# FMC_SINGLE_LPC_BREAKOUT_REVC.net
KiCad netlist of a schematic drawn in Altium Designer
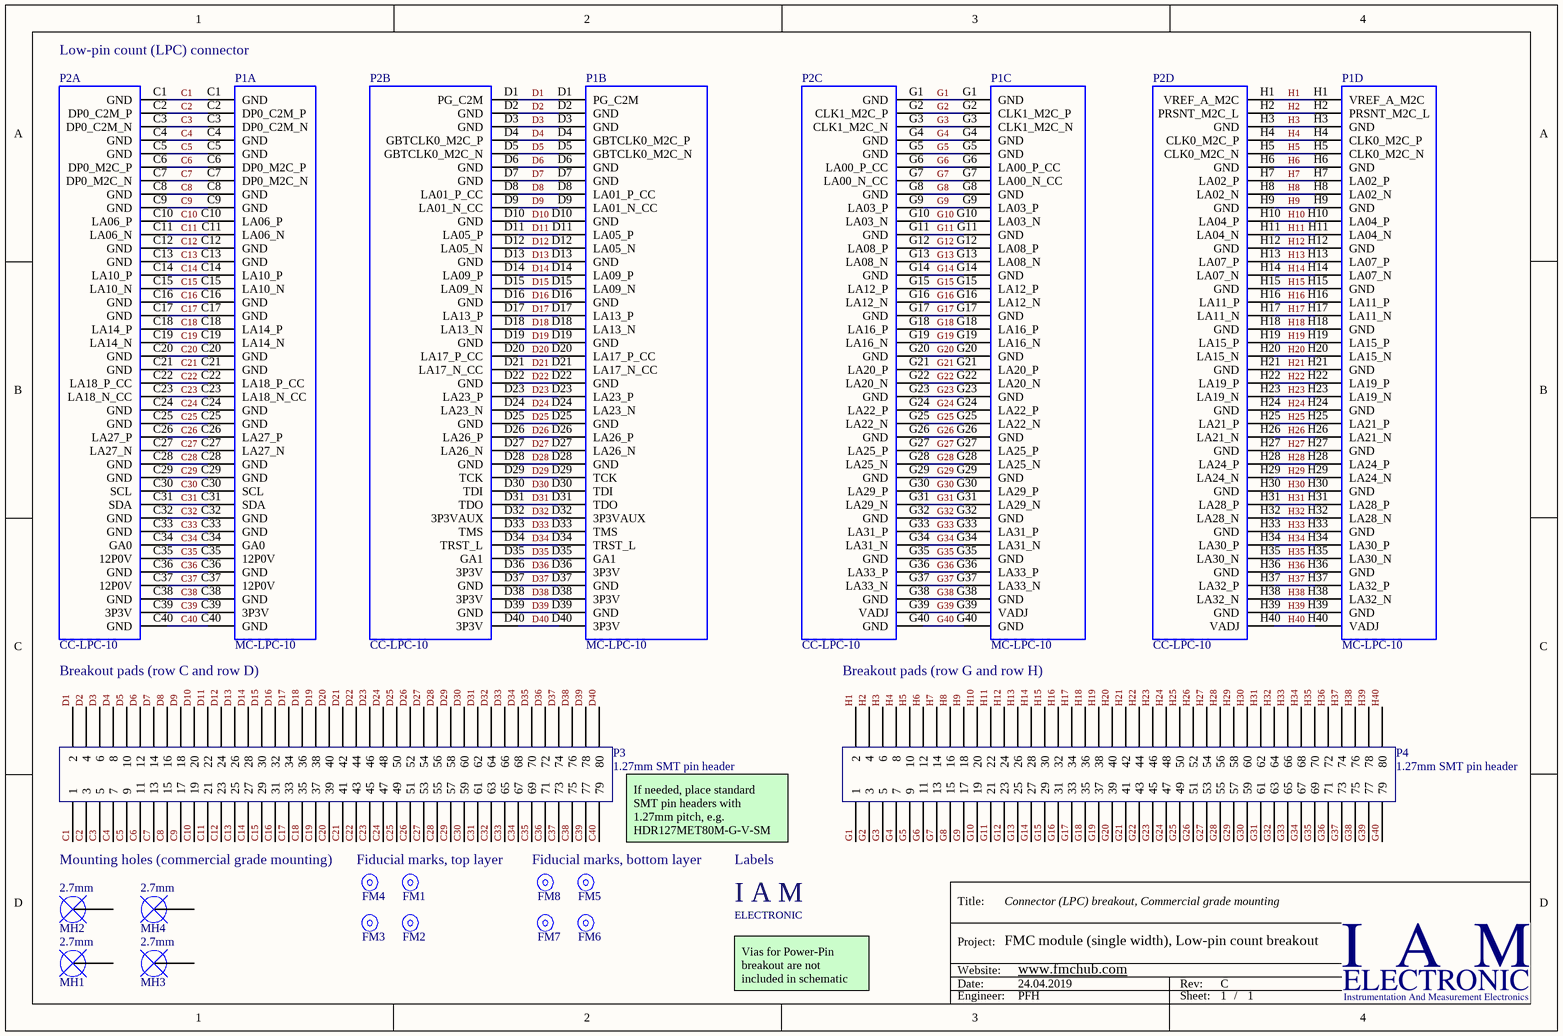
[diagram p0: FMC_SINGLE_LPC_BREAKOUT_REVC.SchDoc]

(export (version "E")
  (design (tool "Eeschema 10.0.6"))
  (components
    (comp (ref "FM1")
      (value "1mm")
      (footprint "FIDUCIAL_MARK_ROUND_RING")
      (description "Fiducial mark, width 1mm, clearance 3mm")
      (libsource (lib "VITA_57_FMC") (part "Fiducial_Mark"))
    )
    (comp (ref "FM2")
      (value "1mm")
      (footprint "FIDUCIAL_MARK_ROUND_RING")
      (description "Fiducial mark, width 1mm, clearance 3mm")
      (libsource (lib "VITA_57_FMC") (part "Fiducial_Mark"))
    )
    (comp (ref "FM3")
      (value "1mm")
      (footprint "FIDUCIAL_MARK_ROUND_RING")
      (description "Fiducial mark, width 1mm, clearance 3mm")
      (libsource (lib "VITA_57_FMC") (part "Fiducial_Mark"))
    )
    (comp (ref "FM4")
      (value "1mm")
      (footprint "FIDUCIAL_MARK_ROUND_RING")
      (description "Fiducial mark, width 1mm, clearance 3mm")
      (libsource (lib "VITA_57_FMC") (part "Fiducial_Mark"))
    )
    (comp (ref "FM5")
      (value "1mm")
      (footprint "FIDUCIAL_MARK_ROUND_RING")
      (description "Fiducial mark, width 1mm, clearance 3mm")
      (libsource (lib "VITA_57_FMC") (part "Fiducial_Mark"))
    )
    (comp (ref "FM6")
      (value "1mm")
      (footprint "FIDUCIAL_MARK_ROUND_RING")
      (description "Fiducial mark, width 1mm, clearance 3mm")
      (libsource (lib "VITA_57_FMC") (part "Fiducial_Mark"))
    )
    (comp (ref "FM7")
      (value "1mm")
      (footprint "FIDUCIAL_MARK_ROUND_RING")
      (description "Fiducial mark, width 1mm, clearance 3mm")
      (libsource (lib "VITA_57_FMC") (part "Fiducial_Mark"))
    )
    (comp (ref "FM8")
      (value "1mm")
      (footprint "FIDUCIAL_MARK_ROUND_RING")
      (description "Fiducial mark, width 1mm, clearance 3mm")
      (libsource (lib "VITA_57_FMC") (part "Fiducial_Mark"))
    )
    (comp (ref "MH1")
      (value "2.7mm")
      (footprint "Mounting_Hole_Plated_2.7mm - d3.1mm")
      (description "Mounting hole, hole size 2.7mm")
      (libsource (lib "VITA_57_FMC") (part "Mounting_Hole_2.7mm"))
    )
    (comp (ref "MH2")
      (value "2.7mm")
      (footprint "Mounting_Hole_Plated_2.7mm - d3.1mm")
      (description "Mounting hole, hole size 2.7mm")
      (libsource (lib "VITA_57_FMC") (part "Mounting_Hole_2.7mm"))
    )
    (comp (ref "MH3")
      (value "2.7mm")
      (footprint "Mounting_Hole_Plated_2.7mm-COVERED")
      (description "Mounting hole, hole size 2.7mm")
      (libsource (lib "VITA_57_FMC") (part "Mounting_Hole_2.7mm"))
    )
    (comp (ref "MH4")
      (value "2.7mm")
      (footprint "Mounting_Hole_Plated_2.7mm-COVERED")
      (description "Mounting hole, hole size 2.7mm")
      (libsource (lib "VITA_57_FMC") (part "Mounting_Hole_2.7mm"))
    )
    (comp (ref "P1")
      (value "MC-LPC-10")
      (footprint "ASP-134604-01")
      (description "MC-LPC-10, FMC Low-pin count connector, lead free, 160 I/Os, male, 10 mm mated stack height")
      (fields (field (name "MANUFACTURER") "Samtec") (field (name "PART") "ASP-134604-01"))
      (libsource (lib "VITA_57_FMC") (part "MC-LPC-10"))
    )
    (comp (ref "P2")
      (value "CC-LPC-10")
      (footprint "ASP-134603-01")
      (description "CC-LPC-10, FMC Low-pin count connector, lead free, 160 I/Os, female, 10 mm mated stack height")
      (fields (field (name "MANUFACTURER") "Samtec") (field (name "PART") "ASP-134603-01"))
      (libsource (lib "VITA_57_FMC") (part "CC-LPC-10"))
    )
    (comp (ref "P3")
      (value "1.27mm SMT pin header")
      (footprint "FTS-140-01-L-DV-A_NO_PASTE")
      (description "1.27 MM 80 PIN VERTICAL MALE HEADER")
      (fields (field (name "PART") "FTS-140-01-L-DV-A") (field (name "MANUFACTURER") "Samtec"))
      (libsource (lib "FTS-140") (part "FTS-140-X-DV"))
    )
    (comp (ref "P4")
      (value "1.27mm SMT pin header")
      (footprint "FTS-140-01-L-DV-A_NO_PASTE")
      (description "1.27 MM 80 PIN VERTICAL MALE HEADER")
      (fields (field (name "PART") "FTS-140-01-L-DV-A") (field (name "MANUFACTURER") "Samtec"))
      (libsource (lib "FTS-140") (part "FTS-140-X-DV"))
    )
    (comp (ref "STR1")
      (value "IAM LOGO")
      (footprint "IAM LOGO - MEDIUM")
      (description "I A M E L E C T R O N I C - Logo")
      (fields (field (name "MANUFACTURER") "IAM ELECTRONIC") (field (name "PART") "Logo"))
      (libsource (lib "IAM_LOGOS") (part "IAM_LOGO"))
    )
  )
  (nets
    (net (code "1") (name "/C1") (class "Default")
      (node (ref "P1") (pin "C1") (pinfunction "GND_C1") (pintype "passive"))
      (node (ref "P2") (pin "C1") (pinfunction "GND_C1") (pintype "passive"))
      (node (ref "P3") (pin "1") (pinfunction "1_1") (pintype "passive"))
    )
    (net (code "2") (name "/C2") (class "Default")
      (node (ref "P1") (pin "C2") (pinfunction "DP0_C2M_P_C2") (pintype "passive"))
      (node (ref "P2") (pin "C2") (pinfunction "DP0_C2M_P_C2") (pintype "passive"))
      (node (ref "P3") (pin "3") (pinfunction "3_3") (pintype "passive"))
    )
    (net (code "3") (name "/C3") (class "Default")
      (node (ref "P1") (pin "C3") (pinfunction "DP0_C2M_N_C3") (pintype "passive"))
      (node (ref "P2") (pin "C3") (pinfunction "DP0_C2M_N_C3") (pintype "passive"))
      (node (ref "P3") (pin "5") (pinfunction "5_5") (pintype "passive"))
    )
    (net (code "4") (name "/C4") (class "Default")
      (node (ref "P1") (pin "C4") (pinfunction "GND_C4") (pintype "passive"))
      (node (ref "P2") (pin "C4") (pinfunction "GND_C4") (pintype "passive"))
      (node (ref "P3") (pin "7") (pinfunction "7_7") (pintype "passive"))
    )
    (net (code "5") (name "/C5") (class "Default")
      (node (ref "P1") (pin "C5") (pinfunction "GND_C5") (pintype "passive"))
      (node (ref "P2") (pin "C5") (pinfunction "GND_C5") (pintype "passive"))
      (node (ref "P3") (pin "9") (pinfunction "9_9") (pintype "passive"))
    )
    (net (code "6") (name "/C6") (class "Default")
      (node (ref "P1") (pin "C6") (pinfunction "DP0_M2C_P_C6") (pintype "passive"))
      (node (ref "P2") (pin "C6") (pinfunction "DP0_M2C_P_C6") (pintype "passive"))
      (node (ref "P3") (pin "11") (pinfunction "11_11") (pintype "passive"))
    )
    (net (code "7") (name "/C7") (class "Default")
      (node (ref "P1") (pin "C7") (pinfunction "DP0_M2C_N_C7") (pintype "passive"))
      (node (ref "P2") (pin "C7") (pinfunction "DP0_M2C_N_C7") (pintype "passive"))
      (node (ref "P3") (pin "13") (pinfunction "13_13") (pintype "passive"))
    )
    (net (code "8") (name "/C8") (class "Default")
      (node (ref "P1") (pin "C8") (pinfunction "GND_C8") (pintype "passive"))
      (node (ref "P2") (pin "C8") (pinfunction "GND_C8") (pintype "passive"))
      (node (ref "P3") (pin "15") (pinfunction "15_15") (pintype "passive"))
    )
    (net (code "9") (name "/C9") (class "Default")
      (node (ref "P1") (pin "C9") (pinfunction "GND_C9") (pintype "passive"))
      (node (ref "P2") (pin "C9") (pinfunction "GND_C9") (pintype "passive"))
      (node (ref "P3") (pin "17") (pinfunction "17_17") (pintype "passive"))
    )
    (net (code "10") (name "/C10") (class "Default")
      (node (ref "P1") (pin "C10") (pinfunction "LA06_P_C10") (pintype "passive"))
      (node (ref "P2") (pin "C10") (pinfunction "LA06_P_C10") (pintype "passive"))
      (node (ref "P3") (pin "19") (pinfunction "19_19") (pintype "passive"))
    )
    (net (code "11") (name "/C11") (class "Default")
      (node (ref "P1") (pin "C11") (pinfunction "LA06_N_C11") (pintype "passive"))
      (node (ref "P2") (pin "C11") (pinfunction "LA06_N_C11") (pintype "passive"))
      (node (ref "P3") (pin "21") (pinfunction "21_21") (pintype "passive"))
    )
    (net (code "12") (name "/C12") (class "Default")
      (node (ref "P1") (pin "C12") (pinfunction "GND_C12") (pintype "passive"))
      (node (ref "P2") (pin "C12") (pinfunction "GND_C12") (pintype "passive"))
      (node (ref "P3") (pin "23") (pinfunction "23_23") (pintype "passive"))
    )
    (net (code "13") (name "/C13") (class "Default")
      (node (ref "P1") (pin "C13") (pinfunction "GND_C13") (pintype "passive"))
      (node (ref "P2") (pin "C13") (pinfunction "GND_C13") (pintype "passive"))
      (node (ref "P3") (pin "25") (pinfunction "25_25") (pintype "passive"))
    )
    (net (code "14") (name "/C14") (class "Default")
      (node (ref "P1") (pin "C14") (pinfunction "LA10_P_C14") (pintype "passive"))
      (node (ref "P2") (pin "C14") (pinfunction "LA10_P_C14") (pintype "passive"))
      (node (ref "P3") (pin "27") (pinfunction "27_27") (pintype "passive"))
    )
    (net (code "15") (name "/C15") (class "Default")
      (node (ref "P1") (pin "C15") (pinfunction "LA10_N_C15") (pintype "passive"))
      (node (ref "P2") (pin "C15") (pinfunction "LA10_N_C15") (pintype "passive"))
      (node (ref "P3") (pin "29") (pinfunction "29_29") (pintype "passive"))
    )
    (net (code "16") (name "/C16") (class "Default")
      (node (ref "P1") (pin "C16") (pinfunction "GND_C16") (pintype "passive"))
      (node (ref "P2") (pin "C16") (pinfunction "GND_C16") (pintype "passive"))
      (node (ref "P3") (pin "31") (pinfunction "31_31") (pintype "passive"))
    )
    (net (code "17") (name "/C17") (class "Default")
      (node (ref "P1") (pin "C17") (pinfunction "GND_C17") (pintype "passive"))
      (node (ref "P2") (pin "C17") (pinfunction "GND_C17") (pintype "passive"))
      (node (ref "P3") (pin "33") (pinfunction "33_33") (pintype "passive"))
    )
    (net (code "18") (name "/C18") (class "Default")
      (node (ref "P1") (pin "C18") (pinfunction "LA14_P_C18") (pintype "passive"))
      (node (ref "P2") (pin "C18") (pinfunction "LA14_P_C18") (pintype "passive"))
      (node (ref "P3") (pin "35") (pinfunction "35_35") (pintype "passive"))
    )
    (net (code "19") (name "/C19") (class "Default")
      (node (ref "P1") (pin "C19") (pinfunction "LA14_N_C19") (pintype "passive"))
      (node (ref "P2") (pin "C19") (pinfunction "LA14_N_C19") (pintype "passive"))
      (node (ref "P3") (pin "37") (pinfunction "37_37") (pintype "passive"))
    )
    (net (code "20") (name "/C20") (class "Default")
      (node (ref "P1") (pin "C20") (pinfunction "GND_C20") (pintype "passive"))
      (node (ref "P2") (pin "C20") (pinfunction "GND_C20") (pintype "passive"))
      (node (ref "P3") (pin "39") (pinfunction "39_39") (pintype "passive"))
    )
    (net (code "21") (name "/C21") (class "Default")
      (node (ref "P1") (pin "C21") (pinfunction "GND_C21") (pintype "passive"))
      (node (ref "P2") (pin "C21") (pinfunction "GND_C21") (pintype "passive"))
      (node (ref "P3") (pin "41") (pinfunction "41_41") (pintype "passive"))
    )
    (net (code "22") (name "/C22") (class "Default")
      (node (ref "P1") (pin "C22") (pinfunction "LA18_P_CC_C22") (pintype "passive"))
      (node (ref "P2") (pin "C22") (pinfunction "LA18_P_CC_C22") (pintype "passive"))
      (node (ref "P3") (pin "43") (pinfunction "43_43") (pintype "passive"))
    )
    (net (code "23") (name "/C23") (class "Default")
      (node (ref "P1") (pin "C23") (pinfunction "LA18_N_CC_C23") (pintype "passive"))
      (node (ref "P2") (pin "C23") (pinfunction "LA18_N_CC_C23") (pintype "passive"))
      (node (ref "P3") (pin "45") (pinfunction "45_45") (pintype "passive"))
    )
    (net (code "24") (name "/C24") (class "Default")
      (node (ref "P1") (pin "C24") (pinfunction "GND_C24") (pintype "passive"))
      (node (ref "P2") (pin "C24") (pinfunction "GND_C24") (pintype "passive"))
      (node (ref "P3") (pin "47") (pinfunction "47_47") (pintype "passive"))
    )
    (net (code "25") (name "/C25") (class "Default")
      (node (ref "P1") (pin "C25") (pinfunction "GND_C25") (pintype "passive"))
      (node (ref "P2") (pin "C25") (pinfunction "GND_C25") (pintype "passive"))
      (node (ref "P3") (pin "49") (pinfunction "49_49") (pintype "passive"))
    )
    (net (code "26") (name "/C26") (class "Default")
      (node (ref "P1") (pin "C26") (pinfunction "LA27_P_C26") (pintype "passive"))
      (node (ref "P2") (pin "C26") (pinfunction "LA27_P_C26") (pintype "passive"))
      (node (ref "P3") (pin "51") (pinfunction "51_51") (pintype "passive"))
    )
    (net (code "27") (name "/C27") (class "Default")
      (node (ref "P1") (pin "C27") (pinfunction "LA27_N_C27") (pintype "passive"))
      (node (ref "P2") (pin "C27") (pinfunction "LA27_N_C27") (pintype "passive"))
      (node (ref "P3") (pin "53") (pinfunction "53_53") (pintype "passive"))
    )
    (net (code "28") (name "/C28") (class "Default")
      (node (ref "P1") (pin "C28") (pinfunction "GND_C28") (pintype "passive"))
      (node (ref "P2") (pin "C28") (pinfunction "GND_C28") (pintype "passive"))
      (node (ref "P3") (pin "55") (pinfunction "55_55") (pintype "passive"))
    )
    (net (code "29") (name "/C29") (class "Default")
      (node (ref "P1") (pin "C29") (pinfunction "GND_C29") (pintype "passive"))
      (node (ref "P2") (pin "C29") (pinfunction "GND_C29") (pintype "passive"))
      (node (ref "P3") (pin "57") (pinfunction "57_57") (pintype "passive"))
    )
    (net (code "30") (name "/C30") (class "Default")
      (node (ref "P1") (pin "C30") (pinfunction "SCL_C30") (pintype "passive"))
      (node (ref "P2") (pin "C30") (pinfunction "SCL_C30") (pintype "passive"))
      (node (ref "P3") (pin "59") (pinfunction "59_59") (pintype "passive"))
    )
    (net (code "31") (name "/C31") (class "Default")
      (node (ref "P1") (pin "C31") (pinfunction "SDA_C31") (pintype "passive"))
      (node (ref "P2") (pin "C31") (pinfunction "SDA_C31") (pintype "passive"))
      (node (ref "P3") (pin "61") (pinfunction "61_61") (pintype "passive"))
    )
    (net (code "32") (name "/C32") (class "Default")
      (node (ref "P1") (pin "C32") (pinfunction "GND_C32") (pintype "passive"))
      (node (ref "P2") (pin "C32") (pinfunction "GND_C32") (pintype "passive"))
      (node (ref "P3") (pin "63") (pinfunction "63_63") (pintype "passive"))
    )
    (net (code "33") (name "/C33") (class "Default")
      (node (ref "P1") (pin "C33") (pinfunction "GND_C33") (pintype "passive"))
      (node (ref "P2") (pin "C33") (pinfunction "GND_C33") (pintype "passive"))
      (node (ref "P3") (pin "65") (pinfunction "65_65") (pintype "passive"))
    )
    (net (code "34") (name "/C34") (class "Default")
      (node (ref "P1") (pin "C34") (pinfunction "GA0_C34") (pintype "passive"))
      (node (ref "P2") (pin "C34") (pinfunction "GA0_C34") (pintype "passive"))
      (node (ref "P3") (pin "67") (pinfunction "67_67") (pintype "passive"))
    )
    (net (code "35") (name "/C35") (class "Default")
      (node (ref "P1") (pin "C35") (pinfunction "12P0V_C35") (pintype "passive"))
      (node (ref "P2") (pin "C35") (pinfunction "12P0V_C35") (pintype "passive"))
      (node (ref "P3") (pin "69") (pinfunction "69_69") (pintype "passive"))
    )
    (net (code "36") (name "/C36") (class "Default")
      (node (ref "P1") (pin "C36") (pinfunction "GND_C36") (pintype "passive"))
      (node (ref "P2") (pin "C36") (pinfunction "GND_C36") (pintype "passive"))
      (node (ref "P3") (pin "71") (pinfunction "71_71") (pintype "passive"))
    )
    (net (code "37") (name "/C37") (class "Default")
      (node (ref "P1") (pin "C37") (pinfunction "12P0V_C37") (pintype "passive"))
      (node (ref "P2") (pin "C37") (pinfunction "12P0V_C37") (pintype "passive"))
      (node (ref "P3") (pin "73") (pinfunction "73_73") (pintype "passive"))
    )
    (net (code "38") (name "/C38") (class "Default")
      (node (ref "P1") (pin "C38") (pinfunction "GND_C38") (pintype "passive"))
      (node (ref "P2") (pin "C38") (pinfunction "GND_C38") (pintype "passive"))
      (node (ref "P3") (pin "75") (pinfunction "75_75") (pintype "passive"))
    )
    (net (code "39") (name "/C39") (class "Default")
      (node (ref "P1") (pin "C39") (pinfunction "3P3V_C39") (pintype "passive"))
      (node (ref "P2") (pin "C39") (pinfunction "3P3V_C39") (pintype "passive"))
      (node (ref "P3") (pin "77") (pinfunction "77_77") (pintype "passive"))
    )
    (net (code "40") (name "/C40") (class "Default")
      (node (ref "P1") (pin "C40") (pinfunction "GND_C40") (pintype "passive"))
      (node (ref "P2") (pin "C40") (pinfunction "GND_C40") (pintype "passive"))
      (node (ref "P3") (pin "79") (pinfunction "79_79") (pintype "passive"))
    )
    (net (code "41") (name "/D1") (class "Default")
      (node (ref "P1") (pin "D1") (pinfunction "PG_C2M_D1") (pintype "passive"))
      (node (ref "P2") (pin "D1") (pinfunction "PG_C2M_D1") (pintype "passive"))
      (node (ref "P3") (pin "2") (pinfunction "2_2") (pintype "passive"))
    )
    (net (code "42") (name "/D2") (class "Default")
      (node (ref "P1") (pin "D2") (pinfunction "GND_D2") (pintype "passive"))
      (node (ref "P2") (pin "D2") (pinfunction "GND_D2") (pintype "passive"))
      (node (ref "P3") (pin "4") (pinfunction "4_4") (pintype "passive"))
    )
    (net (code "43") (name "/D3") (class "Default")
      (node (ref "P1") (pin "D3") (pinfunction "GND_D3") (pintype "passive"))
      (node (ref "P2") (pin "D3") (pinfunction "GND_D3") (pintype "passive"))
      (node (ref "P3") (pin "6") (pinfunction "6_6") (pintype "passive"))
    )
    (net (code "44") (name "/D4") (class "Default")
      (node (ref "P1") (pin "D4") (pinfunction "GBTCLK0_M2C_P_D4") (pintype "passive"))
      (node (ref "P2") (pin "D4") (pinfunction "GBTCLK0_M2C_P_D4") (pintype "passive"))
      (node (ref "P3") (pin "8") (pinfunction "8_8") (pintype "passive"))
    )
    (net (code "45") (name "/D5") (class "Default")
      (node (ref "P1") (pin "D5") (pinfunction "GBTCLK0_M2C_N_D5") (pintype "passive"))
      (node (ref "P2") (pin "D5") (pinfunction "GBTCLK0_M2C_N_D5") (pintype "passive"))
      (node (ref "P3") (pin "10") (pinfunction "10_10") (pintype "passive"))
    )
    (net (code "46") (name "/D6") (class "Default")
      (node (ref "P1") (pin "D6") (pinfunction "GND_D6") (pintype "passive"))
      (node (ref "P2") (pin "D6") (pinfunction "GND_D6") (pintype "passive"))
      (node (ref "P3") (pin "12") (pinfunction "12_12") (pintype "passive"))
    )
    (net (code "47") (name "/D7") (class "Default")
      (node (ref "P1") (pin "D7") (pinfunction "GND_D7") (pintype "passive"))
      (node (ref "P2") (pin "D7") (pinfunction "GND_D7") (pintype "passive"))
      (node (ref "P3") (pin "14") (pinfunction "14_14") (pintype "passive"))
    )
    (net (code "48") (name "/D8") (class "Default")
      (node (ref "P1") (pin "D8") (pinfunction "LA01_P_CC_D8") (pintype "passive"))
      (node (ref "P2") (pin "D8") (pinfunction "LA01_P_CC_D8") (pintype "passive"))
      (node (ref "P3") (pin "16") (pinfunction "16_16") (pintype "passive"))
    )
    (net (code "49") (name "/D9") (class "Default")
      (node (ref "P1") (pin "D9") (pinfunction "LA01_N_CC_D9") (pintype "passive"))
      (node (ref "P2") (pin "D9") (pinfunction "LA01_N_CC_D9") (pintype "passive"))
      (node (ref "P3") (pin "18") (pinfunction "18_18") (pintype "passive"))
    )
    (net (code "50") (name "/D10") (class "Default")
      (node (ref "P1") (pin "D10") (pinfunction "GND_D10") (pintype "passive"))
      (node (ref "P2") (pin "D10") (pinfunction "GND_D10") (pintype "passive"))
      (node (ref "P3") (pin "20") (pinfunction "20_20") (pintype "passive"))
    )
    (net (code "51") (name "/D11") (class "Default")
      (node (ref "P1") (pin "D11") (pinfunction "LA05_P_D11") (pintype "passive"))
      (node (ref "P2") (pin "D11") (pinfunction "LA05_P_D11") (pintype "passive"))
      (node (ref "P3") (pin "22") (pinfunction "22_22") (pintype "passive"))
    )
    (net (code "52") (name "/D12") (class "Default")
      (node (ref "P1") (pin "D12") (pinfunction "LA05_N_D12") (pintype "passive"))
      (node (ref "P2") (pin "D12") (pinfunction "LA05_N_D12") (pintype "passive"))
      (node (ref "P3") (pin "24") (pinfunction "24_24") (pintype "passive"))
    )
    (net (code "53") (name "/D13") (class "Default")
      (node (ref "P1") (pin "D13") (pinfunction "GND_D13") (pintype "passive"))
      (node (ref "P2") (pin "D13") (pinfunction "GND_D13") (pintype "passive"))
      (node (ref "P3") (pin "26") (pinfunction "26_26") (pintype "passive"))
    )
    (net (code "54") (name "/D14") (class "Default")
      (node (ref "P1") (pin "D14") (pinfunction "LA09_P_D14") (pintype "passive"))
      (node (ref "P2") (pin "D14") (pinfunction "LA09_P_D14") (pintype "passive"))
      (node (ref "P3") (pin "28") (pinfunction "28_28") (pintype "passive"))
    )
    (net (code "55") (name "/D15") (class "Default")
      (node (ref "P1") (pin "D15") (pinfunction "LA09_N_D15") (pintype "passive"))
      (node (ref "P2") (pin "D15") (pinfunction "LA09_N_D15") (pintype "passive"))
      (node (ref "P3") (pin "30") (pinfunction "30_30") (pintype "passive"))
    )
    (net (code "56") (name "/D16") (class "Default")
      (node (ref "P1") (pin "D16") (pinfunction "GND_D16") (pintype "passive"))
      (node (ref "P2") (pin "D16") (pinfunction "GND_D16") (pintype "passive"))
      (node (ref "P3") (pin "32") (pinfunction "32_32") (pintype "passive"))
    )
    (net (code "57") (name "/D17") (class "Default")
      (node (ref "P1") (pin "D17") (pinfunction "LA13_P_D17") (pintype "passive"))
      (node (ref "P2") (pin "D17") (pinfunction "LA13_P_D17") (pintype "passive"))
      (node (ref "P3") (pin "34") (pinfunction "34_34") (pintype "passive"))
    )
    (net (code "58") (name "/D18") (class "Default")
      (node (ref "P1") (pin "D18") (pinfunction "LA13_N_D18") (pintype "passive"))
      (node (ref "P2") (pin "D18") (pinfunction "LA13_N_D18") (pintype "passive"))
      (node (ref "P3") (pin "36") (pinfunction "36_36") (pintype "passive"))
    )
    (net (code "59") (name "/D19") (class "Default")
      (node (ref "P1") (pin "D19") (pinfunction "GND_D19") (pintype "passive"))
      (node (ref "P2") (pin "D19") (pinfunction "GND_D19") (pintype "passive"))
      (node (ref "P3") (pin "38") (pinfunction "38_38") (pintype "passive"))
    )
    (net (code "60") (name "/D20") (class "Default")
      (node (ref "P1") (pin "D20") (pinfunction "LA17_P_CC_D20") (pintype "passive"))
      (node (ref "P2") (pin "D20") (pinfunction "LA17_P_CC_D20") (pintype "passive"))
      (node (ref "P3") (pin "40") (pinfunction "40_40") (pintype "passive"))
    )
    (net (code "61") (name "/D21") (class "Default")
      (node (ref "P1") (pin "D21") (pinfunction "LA17_N_CC_D21") (pintype "passive"))
      (node (ref "P2") (pin "D21") (pinfunction "LA17_N_CC_D21") (pintype "passive"))
      (node (ref "P3") (pin "42") (pinfunction "42_42") (pintype "passive"))
    )
    (net (code "62") (name "/D22") (class "Default")
      (node (ref "P1") (pin "D22") (pinfunction "GND_D22") (pintype "passive"))
      (node (ref "P2") (pin "D22") (pinfunction "GND_D22") (pintype "passive"))
      (node (ref "P3") (pin "44") (pinfunction "44_44") (pintype "passive"))
    )
    (net (code "63") (name "/D23") (class "Default")
      (node (ref "P1") (pin "D23") (pinfunction "LA23_P_D23") (pintype "passive"))
      (node (ref "P2") (pin "D23") (pinfunction "LA23_P_D23") (pintype "passive"))
      (node (ref "P3") (pin "46") (pinfunction "46_46") (pintype "passive"))
    )
    (net (code "64") (name "/D24") (class "Default")
      (node (ref "P1") (pin "D24") (pinfunction "LA23_N_D24") (pintype "passive"))
      (node (ref "P2") (pin "D24") (pinfunction "LA23_N_D24") (pintype "passive"))
      (node (ref "P3") (pin "48") (pinfunction "48_48") (pintype "passive"))
    )
    (net (code "65") (name "/D25") (class "Default")
      (node (ref "P1") (pin "D25") (pinfunction "GND_D25") (pintype "passive"))
      (node (ref "P2") (pin "D25") (pinfunction "GND_D25") (pintype "passive"))
      (node (ref "P3") (pin "50") (pinfunction "50_50") (pintype "passive"))
    )
    (net (code "66") (name "/D26") (class "Default")
      (node (ref "P1") (pin "D26") (pinfunction "LA26_P_D26") (pintype "passive"))
      (node (ref "P2") (pin "D26") (pinfunction "LA26_P_D26") (pintype "passive"))
      (node (ref "P3") (pin "52") (pinfunction "52_52") (pintype "passive"))
    )
    (net (code "67") (name "/D27") (class "Default")
      (node (ref "P1") (pin "D27") (pinfunction "LA26_N_D27") (pintype "passive"))
      (node (ref "P2") (pin "D27") (pinfunction "LA26_N_D27") (pintype "passive"))
      (node (ref "P3") (pin "54") (pinfunction "54_54") (pintype "passive"))
    )
    (net (code "68") (name "/D28") (class "Default")
      (node (ref "P1") (pin "D28") (pinfunction "GND_D28") (pintype "passive"))
      (node (ref "P2") (pin "D28") (pinfunction "GND_D28") (pintype "passive"))
      (node (ref "P3") (pin "56") (pinfunction "56_56") (pintype "passive"))
    )
    (net (code "69") (name "/D29") (class "Default")
      (node (ref "P1") (pin "D29") (pinfunction "TCK_D29") (pintype "passive"))
      (node (ref "P2") (pin "D29") (pinfunction "TCK_D29") (pintype "passive"))
      (node (ref "P3") (pin "58") (pinfunction "58_58") (pintype "passive"))
    )
    (net (code "70") (name "/D30") (class "Default")
      (node (ref "P1") (pin "D30") (pinfunction "TDI_D30") (pintype "passive"))
      (node (ref "P2") (pin "D30") (pinfunction "TDI_D30") (pintype "passive"))
      (node (ref "P3") (pin "60") (pinfunction "60_60") (pintype "passive"))
    )
    (net (code "71") (name "/D31") (class "Default")
      (node (ref "P1") (pin "D31") (pinfunction "TDO_D31") (pintype "passive"))
      (node (ref "P2") (pin "D31") (pinfunction "TDO_D31") (pintype "passive"))
      (node (ref "P3") (pin "62") (pinfunction "62_62") (pintype "passive"))
    )
    (net (code "72") (name "/D32") (class "Default")
      (node (ref "P1") (pin "D32") (pinfunction "3P3VAUX_D32") (pintype "passive"))
      (node (ref "P2") (pin "D32") (pinfunction "3P3VAUX_D32") (pintype "passive"))
      (node (ref "P3") (pin "64") (pinfunction "64_64") (pintype "passive"))
    )
    (net (code "73") (name "/D33") (class "Default")
      (node (ref "P1") (pin "D33") (pinfunction "TMS_D33") (pintype "passive"))
      (node (ref "P2") (pin "D33") (pinfunction "TMS_D33") (pintype "passive"))
      (node (ref "P3") (pin "66") (pinfunction "66_66") (pintype "passive"))
    )
    (net (code "74") (name "/D34") (class "Default")
      (node (ref "P1") (pin "D34") (pinfunction "TRST_L_D34") (pintype "passive"))
      (node (ref "P2") (pin "D34") (pinfunction "TRST_L_D34") (pintype "passive"))
      (node (ref "P3") (pin "68") (pinfunction "68_68") (pintype "passive"))
    )
    (net (code "75") (name "/D35") (class "Default")
      (node (ref "P1") (pin "D35") (pinfunction "GA1_D35") (pintype "passive"))
      (node (ref "P2") (pin "D35") (pinfunction "GA1_D35") (pintype "passive"))
      (node (ref "P3") (pin "70") (pinfunction "70_70") (pintype "passive"))
    )
    (net (code "76") (name "/D36") (class "Default")
      (node (ref "P1") (pin "D36") (pinfunction "3P3V_D36") (pintype "passive"))
      (node (ref "P2") (pin "D36") (pinfunction "3P3V_D36") (pintype "passive"))
      (node (ref "P3") (pin "72") (pinfunction "72_72") (pintype "passive"))
    )
    (net (code "77") (name "/D37") (class "Default")
      (node (ref "P1") (pin "D37") (pinfunction "GND_D37") (pintype "passive"))
      (node (ref "P2") (pin "D37") (pinfunction "GND_D37") (pintype "passive"))
      (node (ref "P3") (pin "74") (pinfunction "74_74") (pintype "passive"))
    )
    (net (code "78") (name "/D38") (class "Default")
      (node (ref "P1") (pin "D38") (pinfunction "3P3V_D38") (pintype "passive"))
      (node (ref "P2") (pin "D38") (pinfunction "3P3V_D38") (pintype "passive"))
      (node (ref "P3") (pin "76") (pinfunction "76_76") (pintype "passive"))
    )
    (net (code "79") (name "/D39") (class "Default")
      (node (ref "P1") (pin "D39") (pinfunction "GND_D39") (pintype "passive"))
      (node (ref "P2") (pin "D39") (pinfunction "GND_D39") (pintype "passive"))
      (node (ref "P3") (pin "78") (pinfunction "78_78") (pintype "passive"))
    )
    (net (code "80") (name "/D40") (class "Default")
      (node (ref "P1") (pin "D40") (pinfunction "3P3V_D40") (pintype "passive"))
      (node (ref "P2") (pin "D40") (pinfunction "3P3V_D40") (pintype "passive"))
      (node (ref "P3") (pin "80") (pinfunction "80_80") (pintype "passive"))
    )
    (net (code "81") (name "/G1") (class "Default")
      (node (ref "P1") (pin "G1") (pinfunction "GND_G1") (pintype "passive"))
      (node (ref "P2") (pin "G1") (pinfunction "GND_G1") (pintype "passive"))
      (node (ref "P4") (pin "1") (pinfunction "1_1") (pintype "passive"))
    )
    (net (code "82") (name "/G2") (class "Default")
      (node (ref "P1") (pin "G2") (pinfunction "CLK1_M2C_P_G2") (pintype "passive"))
      (node (ref "P2") (pin "G2") (pinfunction "CLK1_M2C_P_G2") (pintype "passive"))
      (node (ref "P4") (pin "3") (pinfunction "3_3") (pintype "passive"))
    )
    (net (code "83") (name "/G3") (class "Default")
      (node (ref "P1") (pin "G3") (pinfunction "CLK1_M2C_N_G3") (pintype "passive"))
      (node (ref "P2") (pin "G3") (pinfunction "CLK1_M2C_N_G3") (pintype "passive"))
      (node (ref "P4") (pin "5") (pinfunction "5_5") (pintype "passive"))
    )
    (net (code "84") (name "/G4") (class "Default")
      (node (ref "P1") (pin "G4") (pinfunction "GND_G4") (pintype "passive"))
      (node (ref "P2") (pin "G4") (pinfunction "GND_G4") (pintype "passive"))
      (node (ref "P4") (pin "7") (pinfunction "7_7") (pintype "passive"))
    )
    (net (code "85") (name "/G5") (class "Default")
      (node (ref "P1") (pin "G5") (pinfunction "GND_G5") (pintype "passive"))
      (node (ref "P2") (pin "G5") (pinfunction "GND_G5") (pintype "passive"))
      (node (ref "P4") (pin "9") (pinfunction "9_9") (pintype "passive"))
    )
    (net (code "86") (name "/G6") (class "Default")
      (node (ref "P1") (pin "G6") (pinfunction "LA00_P_CC_G6") (pintype "passive"))
      (node (ref "P2") (pin "G6") (pinfunction "LA00_P_CC_G6") (pintype "passive"))
      (node (ref "P4") (pin "11") (pinfunction "11_11") (pintype "passive"))
    )
    (net (code "87") (name "/G7") (class "Default")
      (node (ref "P1") (pin "G7") (pinfunction "LA00_N_CC_G7") (pintype "passive"))
      (node (ref "P2") (pin "G7") (pinfunction "LA00_N_CC_G7") (pintype "passive"))
      (node (ref "P4") (pin "13") (pinfunction "13_13") (pintype "passive"))
    )
    (net (code "88") (name "/G8") (class "Default")
      (node (ref "P1") (pin "G8") (pinfunction "GND_G8") (pintype "passive"))
      (node (ref "P2") (pin "G8") (pinfunction "GND_G8") (pintype "passive"))
      (node (ref "P4") (pin "15") (pinfunction "15_15") (pintype "passive"))
    )
    (net (code "89") (name "/G9") (class "Default")
      (node (ref "P1") (pin "G9") (pinfunction "LA03_P_G9") (pintype "passive"))
      (node (ref "P2") (pin "G9") (pinfunction "LA03_P_G9") (pintype "passive"))
      (node (ref "P4") (pin "17") (pinfunction "17_17") (pintype "passive"))
    )
    (net (code "90") (name "/G10") (class "Default")
      (node (ref "P1") (pin "G10") (pinfunction "LA03_N_G10") (pintype "passive"))
      (node (ref "P2") (pin "G10") (pinfunction "LA03_N_G10") (pintype "passive"))
      (node (ref "P4") (pin "19") (pinfunction "19_19") (pintype "passive"))
    )
    (net (code "91") (name "/G11") (class "Default")
      (node (ref "P1") (pin "G11") (pinfunction "GND_G11") (pintype "passive"))
      (node (ref "P2") (pin "G11") (pinfunction "GND_G11") (pintype "passive"))
      (node (ref "P4") (pin "21") (pinfunction "21_21") (pintype "passive"))
    )
    (net (code "92") (name "/G12") (class "Default")
      (node (ref "P1") (pin "G12") (pinfunction "LA08_P_G12") (pintype "passive"))
      (node (ref "P2") (pin "G12") (pinfunction "LA08_P_G12") (pintype "passive"))
      (node (ref "P4") (pin "23") (pinfunction "23_23") (pintype "passive"))
    )
    (net (code "93") (name "/G13") (class "Default")
      (node (ref "P1") (pin "G13") (pinfunction "LA08_N_G13") (pintype "passive"))
      (node (ref "P2") (pin "G13") (pinfunction "LA08_N_G13") (pintype "passive"))
      (node (ref "P4") (pin "25") (pinfunction "25_25") (pintype "passive"))
    )
    (net (code "94") (name "/G14") (class "Default")
      (node (ref "P1") (pin "G14") (pinfunction "GND_G14") (pintype "passive"))
      (node (ref "P2") (pin "G14") (pinfunction "GND_G14") (pintype "passive"))
      (node (ref "P4") (pin "27") (pinfunction "27_27") (pintype "passive"))
    )
    (net (code "95") (name "/G15") (class "Default")
      (node (ref "P1") (pin "G15") (pinfunction "LA12_P_G15") (pintype "passive"))
      (node (ref "P2") (pin "G15") (pinfunction "LA12_P_G15") (pintype "passive"))
      (node (ref "P4") (pin "29") (pinfunction "29_29") (pintype "passive"))
    )
    (net (code "96") (name "/G16") (class "Default")
      (node (ref "P1") (pin "G16") (pinfunction "LA12_N_G16") (pintype "passive"))
      (node (ref "P2") (pin "G16") (pinfunction "LA12_N_G16") (pintype "passive"))
      (node (ref "P4") (pin "31") (pinfunction "31_31") (pintype "passive"))
    )
    (net (code "97") (name "/G17") (class "Default")
      (node (ref "P1") (pin "G17") (pinfunction "GND_G17") (pintype "passive"))
      (node (ref "P2") (pin "G17") (pinfunction "GND_G17") (pintype "passive"))
      (node (ref "P4") (pin "33") (pinfunction "33_33") (pintype "passive"))
    )
    (net (code "98") (name "/G18") (class "Default")
      (node (ref "P1") (pin "G18") (pinfunction "LA16_P_G18") (pintype "passive"))
      (node (ref "P2") (pin "G18") (pinfunction "LA16_P_G18") (pintype "passive"))
      (node (ref "P4") (pin "35") (pinfunction "35_35") (pintype "passive"))
    )
    (net (code "99") (name "/G19") (class "Default")
      (node (ref "P1") (pin "G19") (pinfunction "LA16_N_G19") (pintype "passive"))
      (node (ref "P2") (pin "G19") (pinfunction "LA16_N_G19") (pintype "passive"))
      (node (ref "P4") (pin "37") (pinfunction "37_37") (pintype "passive"))
    )
    (net (code "100") (name "/G20") (class "Default")
      (node (ref "P1") (pin "G20") (pinfunction "GND_G20") (pintype "passive"))
      (node (ref "P2") (pin "G20") (pinfunction "GND_G20") (pintype "passive"))
      (node (ref "P4") (pin "39") (pinfunction "39_39") (pintype "passive"))
    )
    (net (code "101") (name "/G21") (class "Default")
      (node (ref "P1") (pin "G21") (pinfunction "LA20_P_G21") (pintype "passive"))
      (node (ref "P2") (pin "G21") (pinfunction "LA20_P_G21") (pintype "passive"))
      (node (ref "P4") (pin "41") (pinfunction "41_41") (pintype "passive"))
    )
    (net (code "102") (name "/G22") (class "Default")
      (node (ref "P1") (pin "G22") (pinfunction "LA20_N_G22") (pintype "passive"))
      (node (ref "P2") (pin "G22") (pinfunction "LA20_N_G22") (pintype "passive"))
      (node (ref "P4") (pin "43") (pinfunction "43_43") (pintype "passive"))
    )
    (net (code "103") (name "/G23") (class "Default")
      (node (ref "P1") (pin "G23") (pinfunction "GND_G23") (pintype "passive"))
      (node (ref "P2") (pin "G23") (pinfunction "GND_G23") (pintype "passive"))
      (node (ref "P4") (pin "45") (pinfunction "45_45") (pintype "passive"))
    )
    (net (code "104") (name "/G24") (class "Default")
      (node (ref "P1") (pin "G24") (pinfunction "LA22_P_G24") (pintype "passive"))
      (node (ref "P2") (pin "G24") (pinfunction "LA22_P_G24") (pintype "passive"))
      (node (ref "P4") (pin "47") (pinfunction "47_47") (pintype "passive"))
    )
    (net (code "105") (name "/G25") (class "Default")
      (node (ref "P1") (pin "G25") (pinfunction "LA22_N_G25") (pintype "passive"))
      (node (ref "P2") (pin "G25") (pinfunction "LA22_N_G25") (pintype "passive"))
      (node (ref "P4") (pin "49") (pinfunction "49_49") (pintype "passive"))
    )
    (net (code "106") (name "/G26") (class "Default")
      (node (ref "P1") (pin "G26") (pinfunction "GND_G26") (pintype "passive"))
      (node (ref "P2") (pin "G26") (pinfunction "GND_G26") (pintype "passive"))
      (node (ref "P4") (pin "51") (pinfunction "51_51") (pintype "passive"))
    )
    (net (code "107") (name "/G27") (class "Default")
      (node (ref "P1") (pin "G27") (pinfunction "LA25_P_G27") (pintype "passive"))
      (node (ref "P2") (pin "G27") (pinfunction "LA25_P_G27") (pintype "passive"))
      (node (ref "P4") (pin "53") (pinfunction "53_53") (pintype "passive"))
    )
    (net (code "108") (name "/G28") (class "Default")
      (node (ref "P1") (pin "G28") (pinfunction "LA25_N_G28") (pintype "passive"))
      (node (ref "P2") (pin "G28") (pinfunction "LA25_N_G28") (pintype "passive"))
      (node (ref "P4") (pin "55") (pinfunction "55_55") (pintype "passive"))
    )
    (net (code "109") (name "/G29") (class "Default")
      (node (ref "P1") (pin "G29") (pinfunction "GND_G29") (pintype "passive"))
      (node (ref "P2") (pin "G29") (pinfunction "GND_G29") (pintype "passive"))
      (node (ref "P4") (pin "57") (pinfunction "57_57") (pintype "passive"))
    )
    (net (code "110") (name "/G30") (class "Default")
      (node (ref "P1") (pin "G30") (pinfunction "LA29_P_G30") (pintype "passive"))
      (node (ref "P2") (pin "G30") (pinfunction "LA29_P_G30") (pintype "passive"))
      (node (ref "P4") (pin "59") (pinfunction "59_59") (pintype "passive"))
    )
    (net (code "111") (name "/G31") (class "Default")
      (node (ref "P1") (pin "G31") (pinfunction "LA29_N_G31") (pintype "passive"))
      (node (ref "P2") (pin "G31") (pinfunction "LA29_N_G31") (pintype "passive"))
      (node (ref "P4") (pin "61") (pinfunction "61_61") (pintype "passive"))
    )
    (net (code "112") (name "/G32") (class "Default")
      (node (ref "P1") (pin "G32") (pinfunction "GND_G32") (pintype "passive"))
      (node (ref "P2") (pin "G32") (pinfunction "GND_G32") (pintype "passive"))
      (node (ref "P4") (pin "63") (pinfunction "63_63") (pintype "passive"))
    )
    (net (code "113") (name "/G33") (class "Default")
      (node (ref "P1") (pin "G33") (pinfunction "LA31_P_G33") (pintype "passive"))
      (node (ref "P2") (pin "G33") (pinfunction "LA31_P_G33") (pintype "passive"))
      (node (ref "P4") (pin "65") (pinfunction "65_65") (pintype "passive"))
    )
    (net (code "114") (name "/G34") (class "Default")
      (node (ref "P1") (pin "G34") (pinfunction "LA31_N_G34") (pintype "passive"))
      (node (ref "P2") (pin "G34") (pinfunction "LA31_N_G34") (pintype "passive"))
      (node (ref "P4") (pin "67") (pinfunction "67_67") (pintype "passive"))
    )
    (net (code "115") (name "/G35") (class "Default")
      (node (ref "P1") (pin "G35") (pinfunction "GND_G35") (pintype "passive"))
      (node (ref "P2") (pin "G35") (pinfunction "GND_G35") (pintype "passive"))
      (node (ref "P4") (pin "69") (pinfunction "69_69") (pintype "passive"))
    )
    (net (code "116") (name "/G36") (class "Default")
      (node (ref "P1") (pin "G36") (pinfunction "LA33_P_G36") (pintype "passive"))
      (node (ref "P2") (pin "G36") (pinfunction "LA33_P_G36") (pintype "passive"))
      (node (ref "P4") (pin "71") (pinfunction "71_71") (pintype "passive"))
    )
    (net (code "117") (name "/G37") (class "Default")
      (node (ref "P1") (pin "G37") (pinfunction "LA33_N_G37") (pintype "passive"))
      (node (ref "P2") (pin "G37") (pinfunction "LA33_N_G37") (pintype "passive"))
      (node (ref "P4") (pin "73") (pinfunction "73_73") (pintype "passive"))
    )
    (net (code "118") (name "/G38") (class "Default")
      (node (ref "P1") (pin "G38") (pinfunction "GND_G38") (pintype "passive"))
      (node (ref "P2") (pin "G38") (pinfunction "GND_G38") (pintype "passive"))
      (node (ref "P4") (pin "75") (pinfunction "75_75") (pintype "passive"))
    )
    (net (code "119") (name "/G39") (class "Default")
      (node (ref "P1") (pin "G39") (pinfunction "VADJ_G39") (pintype "passive"))
      (node (ref "P2") (pin "G39") (pinfunction "VADJ_G39") (pintype "passive"))
      (node (ref "P4") (pin "77") (pinfunction "77_77") (pintype "passive"))
    )
    (net (code "120") (name "/G40") (class "Default")
      (node (ref "P1") (pin "G40") (pinfunction "GND_G40") (pintype "passive"))
      (node (ref "P2") (pin "G40") (pinfunction "GND_G40") (pintype "passive"))
      (node (ref "P4") (pin "79") (pinfunction "79_79") (pintype "passive"))
    )
    (net (code "121") (name "/H1") (class "Default")
      (node (ref "P1") (pin "H1") (pinfunction "VREF_A_M2C_H1") (pintype "passive"))
      (node (ref "P2") (pin "H1") (pinfunction "VREF_A_M2C_H1") (pintype "passive"))
      (node (ref "P4") (pin "2") (pinfunction "2_2") (pintype "passive"))
    )
    (net (code "122") (name "/H2") (class "Default")
      (node (ref "P1") (pin "H2") (pinfunction "PRSNT_M2C_L_H2") (pintype "passive"))
      (node (ref "P2") (pin "H2") (pinfunction "PRSNT_M2C_L_H2") (pintype "passive"))
      (node (ref "P4") (pin "4") (pinfunction "4_4") (pintype "passive"))
    )
    (net (code "123") (name "/H3") (class "Default")
      (node (ref "P1") (pin "H3") (pinfunction "GND_H3") (pintype "passive"))
      (node (ref "P2") (pin "H3") (pinfunction "GND_H3") (pintype "passive"))
      (node (ref "P4") (pin "6") (pinfunction "6_6") (pintype "passive"))
    )
    (net (code "124") (name "/H4") (class "Default")
      (node (ref "P1") (pin "H4") (pinfunction "CLK0_M2C_P_H4") (pintype "passive"))
      (node (ref "P2") (pin "H4") (pinfunction "CLK0_M2C_P_H4") (pintype "passive"))
      (node (ref "P4") (pin "8") (pinfunction "8_8") (pintype "passive"))
    )
    (net (code "125") (name "/H5") (class "Default")
      (node (ref "P1") (pin "H5") (pinfunction "CLK0_M2C_N_H5") (pintype "passive"))
      (node (ref "P2") (pin "H5") (pinfunction "CLK0_M2C_N_H5") (pintype "passive"))
      (node (ref "P4") (pin "10") (pinfunction "10_10") (pintype "passive"))
    )
    (net (code "126") (name "/H6") (class "Default")
      (node (ref "P1") (pin "H6") (pinfunction "GND_H6") (pintype "passive"))
      (node (ref "P2") (pin "H6") (pinfunction "GND_H6") (pintype "passive"))
      (node (ref "P4") (pin "12") (pinfunction "12_12") (pintype "passive"))
    )
    (net (code "127") (name "/H7") (class "Default")
      (node (ref "P1") (pin "H7") (pinfunction "LA02_P_H7") (pintype "passive"))
      (node (ref "P2") (pin "H7") (pinfunction "LA02_P_H7") (pintype "passive"))
      (node (ref "P4") (pin "14") (pinfunction "14_14") (pintype "passive"))
    )
    (net (code "128") (name "/H8") (class "Default")
      (node (ref "P1") (pin "H8") (pinfunction "LA02_N_H8") (pintype "passive"))
      (node (ref "P2") (pin "H8") (pinfunction "LA02_N_H8") (pintype "passive"))
      (node (ref "P4") (pin "16") (pinfunction "16_16") (pintype "passive"))
    )
    (net (code "129") (name "/H9") (class "Default")
      (node (ref "P1") (pin "H9") (pinfunction "GND_H9") (pintype "passive"))
      (node (ref "P2") (pin "H9") (pinfunction "GND_H9") (pintype "passive"))
      (node (ref "P4") (pin "18") (pinfunction "18_18") (pintype "passive"))
    )
    (net (code "130") (name "/H10") (class "Default")
      (node (ref "P1") (pin "H10") (pinfunction "LA04_P_H10") (pintype "passive"))
      (node (ref "P2") (pin "H10") (pinfunction "LA04_P_H10") (pintype "passive"))
      (node (ref "P4") (pin "20") (pinfunction "20_20") (pintype "passive"))
    )
    (net (code "131") (name "/H11") (class "Default")
      (node (ref "P1") (pin "H11") (pinfunction "LA04_N_H11") (pintype "passive"))
      (node (ref "P2") (pin "H11") (pinfunction "LA04_N_H11") (pintype "passive"))
      (node (ref "P4") (pin "22") (pinfunction "22_22") (pintype "passive"))
    )
    (net (code "132") (name "/H12") (class "Default")
      (node (ref "P1") (pin "H12") (pinfunction "GND_H12") (pintype "passive"))
      (node (ref "P2") (pin "H12") (pinfunction "GND_H12") (pintype "passive"))
      (node (ref "P4") (pin "24") (pinfunction "24_24") (pintype "passive"))
    )
    (net (code "133") (name "/H13") (class "Default")
      (node (ref "P1") (pin "H13") (pinfunction "LA07_P_H13") (pintype "passive"))
      (node (ref "P2") (pin "H13") (pinfunction "LA07_P_H13") (pintype "passive"))
      (node (ref "P4") (pin "26") (pinfunction "26_26") (pintype "passive"))
    )
    (net (code "134") (name "/H14") (class "Default")
      (node (ref "P1") (pin "H14") (pinfunction "LA07_N_H14") (pintype "passive"))
      (node (ref "P2") (pin "H14") (pinfunction "LA07_N_H14") (pintype "passive"))
      (node (ref "P4") (pin "28") (pinfunction "28_28") (pintype "passive"))
    )
    (net (code "135") (name "/H15") (class "Default")
      (node (ref "P1") (pin "H15") (pinfunction "GND_H15") (pintype "passive"))
      (node (ref "P2") (pin "H15") (pinfunction "GND_H15") (pintype "passive"))
      (node (ref "P4") (pin "30") (pinfunction "30_30") (pintype "passive"))
    )
    (net (code "136") (name "/H16") (class "Default")
      (node (ref "P1") (pin "H16") (pinfunction "LA11_P_H16") (pintype "passive"))
      (node (ref "P2") (pin "H16") (pinfunction "LA11_P_H16") (pintype "passive"))
      (node (ref "P4") (pin "32") (pinfunction "32_32") (pintype "passive"))
    )
    (net (code "137") (name "/H17") (class "Default")
      (node (ref "P1") (pin "H17") (pinfunction "LA11_N_H17") (pintype "passive"))
      (node (ref "P2") (pin "H17") (pinfunction "LA11_N_H17") (pintype "passive"))
      (node (ref "P4") (pin "34") (pinfunction "34_34") (pintype "passive"))
    )
    (net (code "138") (name "/H18") (class "Default")
      (node (ref "P1") (pin "H18") (pinfunction "GND_H18") (pintype "passive"))
      (node (ref "P2") (pin "H18") (pinfunction "GND_H18") (pintype "passive"))
      (node (ref "P4") (pin "36") (pinfunction "36_36") (pintype "passive"))
    )
    (net (code "139") (name "/H19") (class "Default")
      (node (ref "P1") (pin "H19") (pinfunction "LA15_P_H19") (pintype "passive"))
      (node (ref "P2") (pin "H19") (pinfunction "LA15_P_H19") (pintype "passive"))
      (node (ref "P4") (pin "38") (pinfunction "38_38") (pintype "passive"))
    )
    (net (code "140") (name "/H20") (class "Default")
      (node (ref "P1") (pin "H20") (pinfunction "LA15_N_H20") (pintype "passive"))
      (node (ref "P2") (pin "H20") (pinfunction "LA15_N_H20") (pintype "passive"))
      (node (ref "P4") (pin "40") (pinfunction "40_40") (pintype "passive"))
    )
    (net (code "141") (name "/H21") (class "Default")
      (node (ref "P1") (pin "H21") (pinfunction "GND_H21") (pintype "passive"))
      (node (ref "P2") (pin "H21") (pinfunction "GND_H21") (pintype "passive"))
      (node (ref "P4") (pin "42") (pinfunction "42_42") (pintype "passive"))
    )
    (net (code "142") (name "/H22") (class "Default")
      (node (ref "P1") (pin "H22") (pinfunction "LA19_P_H22") (pintype "passive"))
      (node (ref "P2") (pin "H22") (pinfunction "LA19_P_H22") (pintype "passive"))
      (node (ref "P4") (pin "44") (pinfunction "44_44") (pintype "passive"))
    )
    (net (code "143") (name "/H23") (class "Default")
      (node (ref "P1") (pin "H23") (pinfunction "LA19_N_H23") (pintype "passive"))
      (node (ref "P2") (pin "H23") (pinfunction "LA19_N_H23") (pintype "passive"))
      (node (ref "P4") (pin "46") (pinfunction "46_46") (pintype "passive"))
    )
    (net (code "144") (name "/H24") (class "Default")
      (node (ref "P1") (pin "H24") (pinfunction "GND_H24") (pintype "passive"))
      (node (ref "P2") (pin "H24") (pinfunction "GND_H24") (pintype "passive"))
      (node (ref "P4") (pin "48") (pinfunction "48_48") (pintype "passive"))
    )
    (net (code "145") (name "/H25") (class "Default")
      (node (ref "P1") (pin "H25") (pinfunction "LA21_P_H25") (pintype "passive"))
      (node (ref "P2") (pin "H25") (pinfunction "LA21_P_H25") (pintype "passive"))
      (node (ref "P4") (pin "50") (pinfunction "50_50") (pintype "passive"))
    )
    (net (code "146") (name "/H26") (class "Default")
      (node (ref "P1") (pin "H26") (pinfunction "LA21_N_H26") (pintype "passive"))
      (node (ref "P2") (pin "H26") (pinfunction "LA21_N_H26") (pintype "passive"))
      (node (ref "P4") (pin "52") (pinfunction "52_52") (pintype "passive"))
    )
    (net (code "147") (name "/H27") (class "Default")
      (node (ref "P1") (pin "H27") (pinfunction "GND_H27") (pintype "passive"))
      (node (ref "P2") (pin "H27") (pinfunction "GND_H27") (pintype "passive"))
      (node (ref "P4") (pin "54") (pinfunction "54_54") (pintype "passive"))
    )
    (net (code "148") (name "/H28") (class "Default")
      (node (ref "P1") (pin "H28") (pinfunction "LA24_P_H28") (pintype "passive"))
      (node (ref "P2") (pin "H28") (pinfunction "LA24_P_H28") (pintype "passive"))
      (node (ref "P4") (pin "56") (pinfunction "56_56") (pintype "passive"))
    )
    (net (code "149") (name "/H29") (class "Default")
      (node (ref "P1") (pin "H29") (pinfunction "LA24_N_H29") (pintype "passive"))
      (node (ref "P2") (pin "H29") (pinfunction "LA24_N_H29") (pintype "passive"))
      (node (ref "P4") (pin "58") (pinfunction "58_58") (pintype "passive"))
    )
    (net (code "150") (name "/H30") (class "Default")
      (node (ref "P1") (pin "H30") (pinfunction "GND_H30") (pintype "passive"))
      (node (ref "P2") (pin "H30") (pinfunction "GND_H30") (pintype "passive"))
      (node (ref "P4") (pin "60") (pinfunction "60_60") (pintype "passive"))
    )
    (net (code "151") (name "/H31") (class "Default")
      (node (ref "P1") (pin "H31") (pinfunction "LA28_P_H31") (pintype "passive"))
      (node (ref "P2") (pin "H31") (pinfunction "LA28_P_H31") (pintype "passive"))
      (node (ref "P4") (pin "62") (pinfunction "62_62") (pintype "passive"))
    )
    (net (code "152") (name "/H32") (class "Default")
      (node (ref "P1") (pin "H32") (pinfunction "LA28_N_H32") (pintype "passive"))
      (node (ref "P2") (pin "H32") (pinfunction "LA28_N_H32") (pintype "passive"))
      (node (ref "P4") (pin "64") (pinfunction "64_64") (pintype "passive"))
    )
    (net (code "153") (name "/H33") (class "Default")
      (node (ref "P1") (pin "H33") (pinfunction "GND_H33") (pintype "passive"))
      (node (ref "P2") (pin "H33") (pinfunction "GND_H33") (pintype "passive"))
      (node (ref "P4") (pin "66") (pinfunction "66_66") (pintype "passive"))
    )
    (net (code "154") (name "/H34") (class "Default")
      (node (ref "P1") (pin "H34") (pinfunction "LA30_P_H34") (pintype "passive"))
      (node (ref "P2") (pin "H34") (pinfunction "LA30_P_H34") (pintype "passive"))
      (node (ref "P4") (pin "68") (pinfunction "68_68") (pintype "passive"))
    )
    (net (code "155") (name "/H35") (class "Default")
      (node (ref "P1") (pin "H35") (pinfunction "LA30_N_H35") (pintype "passive"))
      (node (ref "P2") (pin "H35") (pinfunction "LA30_N_H35") (pintype "passive"))
      (node (ref "P4") (pin "70") (pinfunction "70_70") (pintype "passive"))
    )
    (net (code "156") (name "/H36") (class "Default")
      (node (ref "P1") (pin "H36") (pinfunction "GND_H36") (pintype "passive"))
      (node (ref "P2") (pin "H36") (pinfunction "GND_H36") (pintype "passive"))
      (node (ref "P4") (pin "72") (pinfunction "72_72") (pintype "passive"))
    )
    (net (code "157") (name "/H37") (class "Default")
      (node (ref "P1") (pin "H37") (pinfunction "LA32_P_H37") (pintype "passive"))
      (node (ref "P2") (pin "H37") (pinfunction "LA32_P_H37") (pintype "passive"))
      (node (ref "P4") (pin "74") (pinfunction "74_74") (pintype "passive"))
    )
    (net (code "158") (name "/H38") (class "Default")
      (node (ref "P1") (pin "H38") (pinfunction "LA32_N_H38") (pintype "passive"))
      (node (ref "P2") (pin "H38") (pinfunction "LA32_N_H38") (pintype "passive"))
      (node (ref "P4") (pin "76") (pinfunction "76_76") (pintype "passive"))
    )
    (net (code "159") (name "/H39") (class "Default")
      (node (ref "P1") (pin "H39") (pinfunction "GND_H39") (pintype "passive"))
      (node (ref "P2") (pin "H39") (pinfunction "GND_H39") (pintype "passive"))
      (node (ref "P4") (pin "78") (pinfunction "78_78") (pintype "passive"))
    )
    (net (code "160") (name "/H40") (class "Default")
      (node (ref "P1") (pin "H40") (pinfunction "VADJ_H40") (pintype "passive"))
      (node (ref "P2") (pin "H40") (pinfunction "VADJ_H40") (pintype "passive"))
      (node (ref "P4") (pin "80") (pinfunction "80_80") (pintype "passive"))
    )
    (net (code "161") (name "unconnected-(FM1-PadFD0)") (class "Default")
      (node (ref "FM1") (pin "FD0") (pinfunction "FD0_FD0") (pintype "passive"))
    )
    (net (code "162") (name "unconnected-(FM2-PadFD0)") (class "Default")
      (node (ref "FM2") (pin "FD0") (pinfunction "FD0_FD0") (pintype "passive"))
    )
    (net (code "163") (name "unconnected-(FM3-PadFD0)") (class "Default")
      (node (ref "FM3") (pin "FD0") (pinfunction "FD0_FD0") (pintype "passive"))
    )
    (net (code "164") (name "unconnected-(FM4-PadFD0)") (class "Default")
      (node (ref "FM4") (pin "FD0") (pinfunction "FD0_FD0") (pintype "passive"))
    )
    (net (code "165") (name "unconnected-(FM5-PadFD0)") (class "Default")
      (node (ref "FM5") (pin "FD0") (pinfunction "FD0_FD0") (pintype "passive"))
    )
    (net (code "166") (name "unconnected-(FM6-PadFD0)") (class "Default")
      (node (ref "FM6") (pin "FD0") (pinfunction "FD0_FD0") (pintype "passive"))
    )
    (net (code "167") (name "unconnected-(FM7-PadFD0)") (class "Default")
      (node (ref "FM7") (pin "FD0") (pinfunction "FD0_FD0") (pintype "passive"))
    )
    (net (code "168") (name "unconnected-(FM8-PadFD0)") (class "Default")
      (node (ref "FM8") (pin "FD0") (pinfunction "FD0_FD0") (pintype "passive"))
    )
    (net (code "169") (name "unconnected-(MH1-Pad0)") (class "Default")
      (node (ref "MH1") (pin "0") (pinfunction "0_0") (pintype "passive"))
    )
    (net (code "170") (name "unconnected-(MH2-Pad0)") (class "Default")
      (node (ref "MH2") (pin "0") (pinfunction "0_0") (pintype "passive"))
    )
    (net (code "171") (name "unconnected-(MH3-Pad0)") (class "Default")
      (node (ref "MH3") (pin "0") (pinfunction "0_0") (pintype "passive"))
    )
    (net (code "172") (name "unconnected-(MH4-Pad0)") (class "Default")
      (node (ref "MH4") (pin "0") (pinfunction "0_0") (pintype "passive"))
    )
  )
)
